# regsimple2addfp.net
KiCad netlist of a schematic drawn in EAGLE
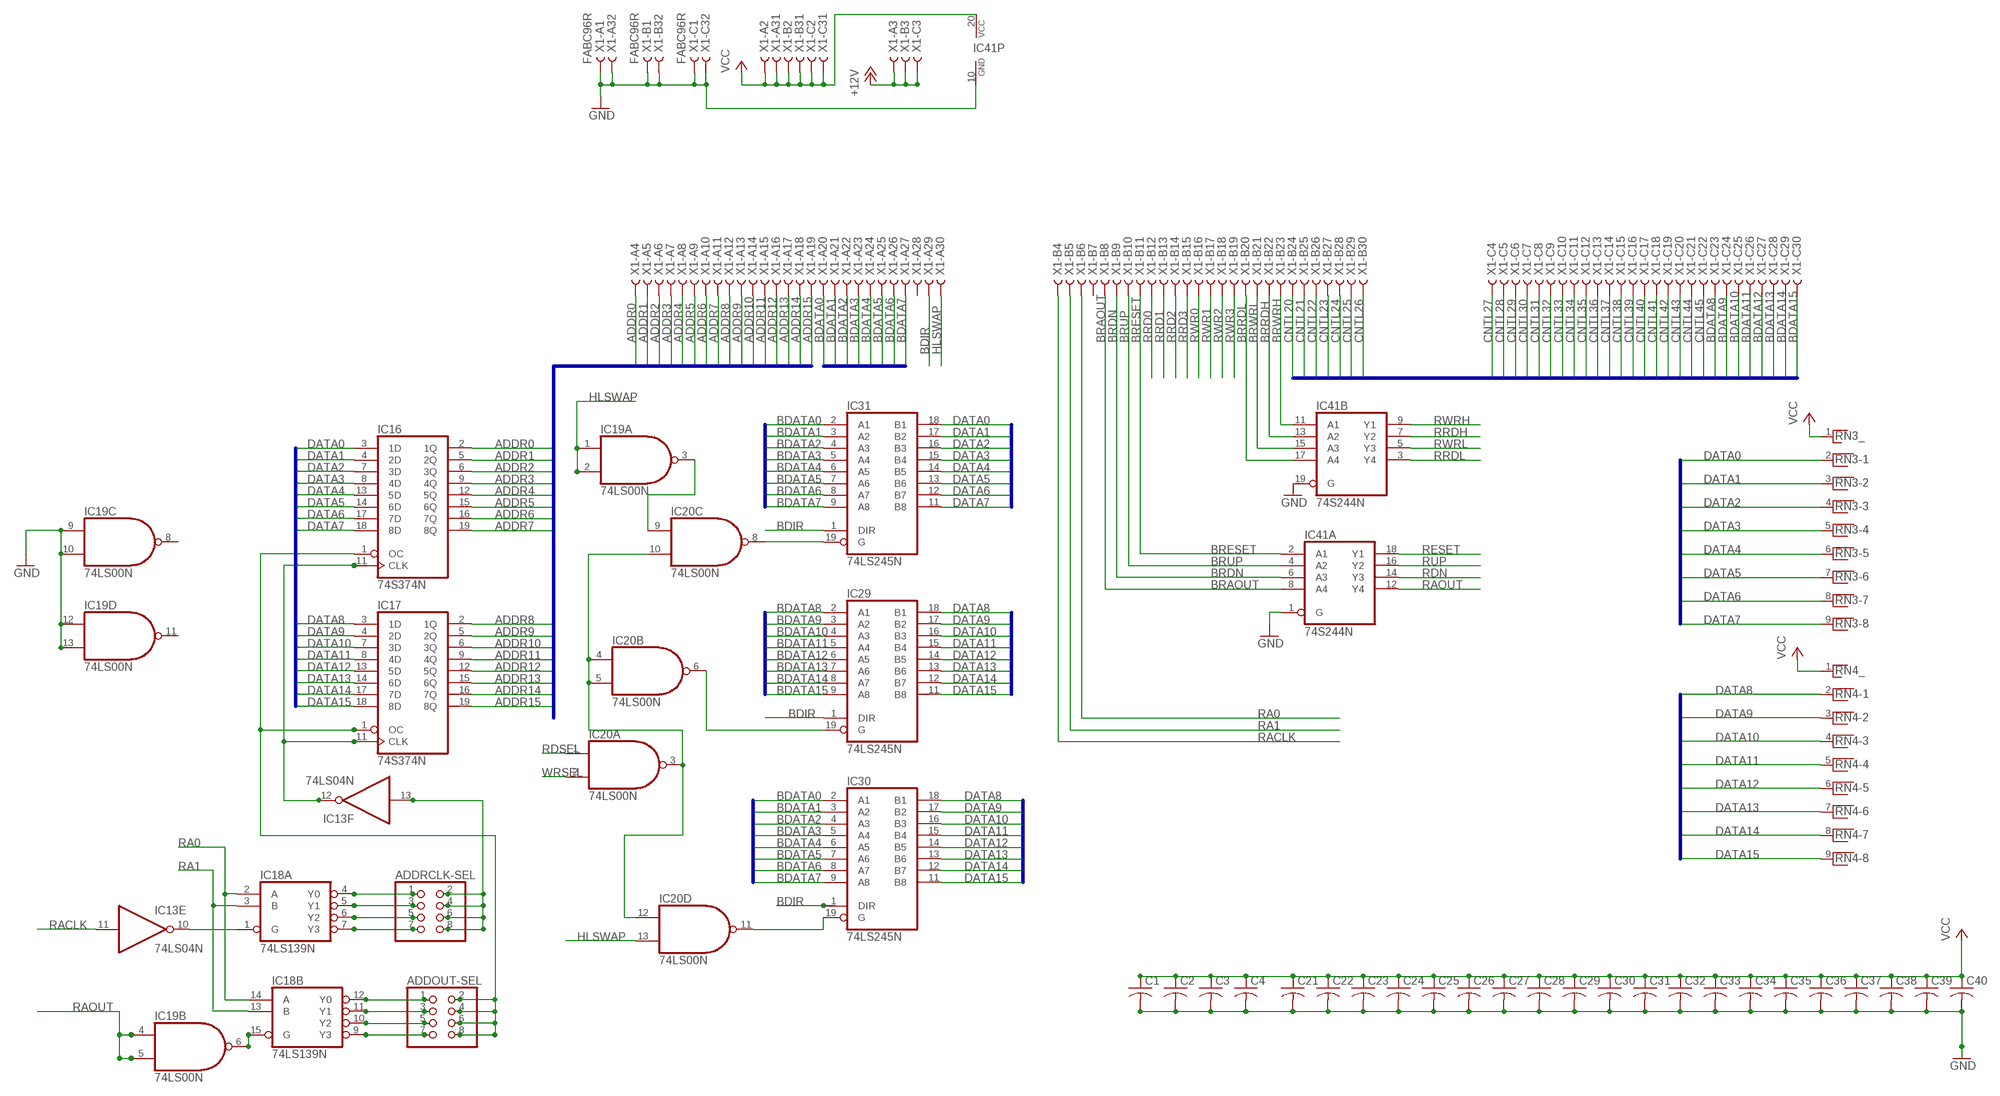
[diagram p0: schematic, sheet 1]
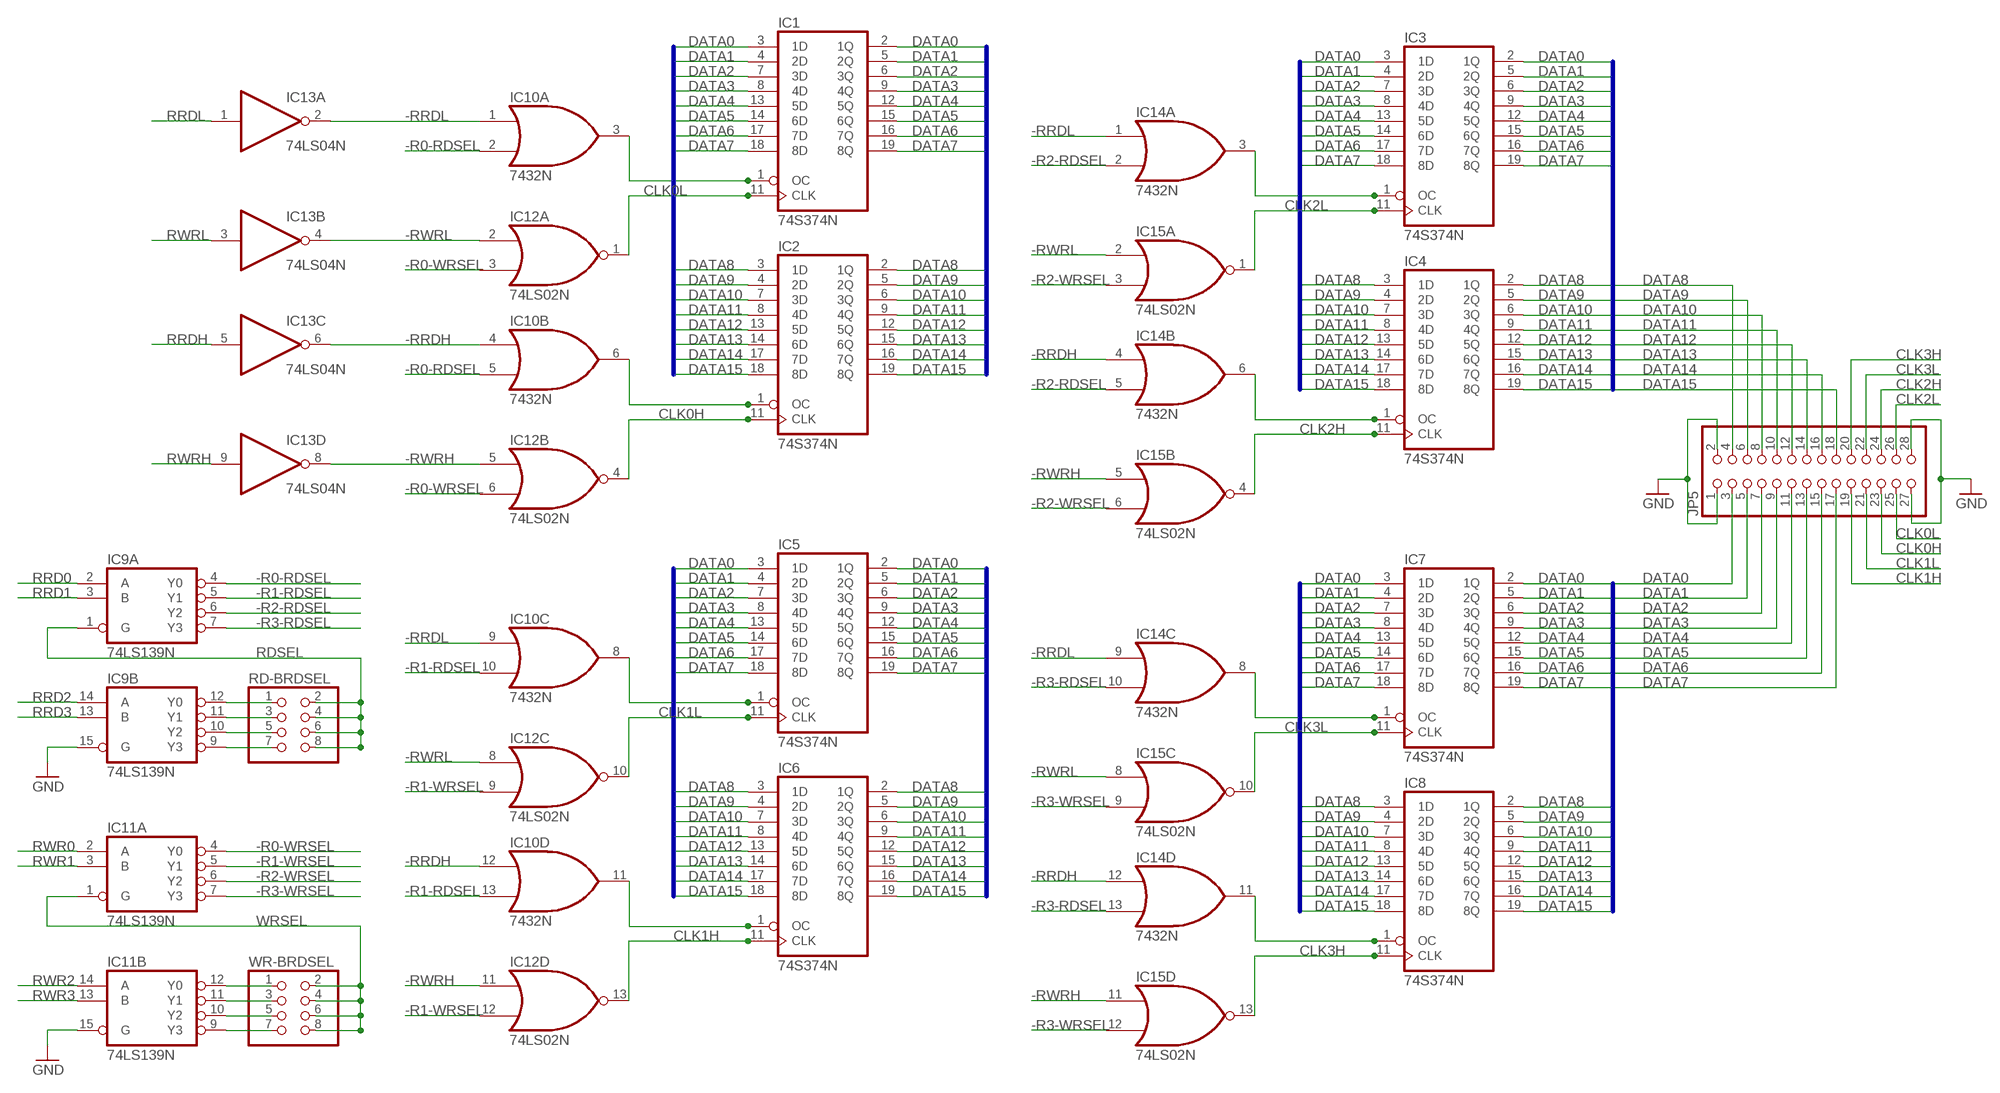
[diagram p1: schematic, sheet 2]

(export (version "E")
  (design (tool "Eeschema 10.0.6"))
  (components
    (comp (ref "ADDOUT-SEL")
      (value "PINHD-2X4")
      (footprint "eagle-import:2X04")
      (libsource (lib "eagle-import") (part "PINHD-2X4"))
    )
    (comp (ref "ADDRCLK-SEL")
      (value "PINHD-2X4")
      (footprint "eagle-import:2X04")
      (libsource (lib "eagle-import") (part "PINHD-2X4"))
    )
    (comp (ref "C1")
      (value "C-US025-040X050")
      (footprint "eagle-import:C025-040X050")
      (libsource (lib "eagle-import") (part "C-US025-040X050"))
    )
    (comp (ref "C2")
      (value "C-US025-040X050")
      (footprint "eagle-import:C025-040X050")
      (libsource (lib "eagle-import") (part "C-US025-040X050"))
    )
    (comp (ref "C3")
      (value "C-US025-040X050")
      (footprint "eagle-import:C025-040X050")
      (libsource (lib "eagle-import") (part "C-US025-040X050"))
    )
    (comp (ref "C4")
      (value "C-US025-040X050")
      (footprint "eagle-import:C025-040X050")
      (libsource (lib "eagle-import") (part "C-US025-040X050"))
    )
    (comp (ref "C21")
      (value "C-US025-040X050")
      (footprint "eagle-import:C025-040X050")
      (libsource (lib "eagle-import") (part "C-US025-040X050"))
    )
    (comp (ref "C22")
      (value "C-US025-040X050")
      (footprint "eagle-import:C025-040X050")
      (libsource (lib "eagle-import") (part "C-US025-040X050"))
    )
    (comp (ref "C23")
      (value "C-US025-040X050")
      (footprint "eagle-import:C025-040X050")
      (libsource (lib "eagle-import") (part "C-US025-040X050"))
    )
    (comp (ref "C24")
      (value "C-US025-040X050")
      (footprint "eagle-import:C025-040X050")
      (libsource (lib "eagle-import") (part "C-US025-040X050"))
    )
    (comp (ref "C25")
      (value "C-US025-040X050")
      (footprint "eagle-import:C025-040X050")
      (libsource (lib "eagle-import") (part "C-US025-040X050"))
    )
    (comp (ref "C26")
      (value "C-US025-040X050")
      (footprint "eagle-import:C025-040X050")
      (libsource (lib "eagle-import") (part "C-US025-040X050"))
    )
    (comp (ref "C27")
      (value "C-US025-040X050")
      (footprint "eagle-import:C025-040X050")
      (libsource (lib "eagle-import") (part "C-US025-040X050"))
    )
    (comp (ref "C28")
      (value "C-US025-040X050")
      (footprint "eagle-import:C025-040X050")
      (libsource (lib "eagle-import") (part "C-US025-040X050"))
    )
    (comp (ref "C29")
      (value "C-US025-040X050")
      (footprint "eagle-import:C025-040X050")
      (libsource (lib "eagle-import") (part "C-US025-040X050"))
    )
    (comp (ref "C30")
      (value "C-US025-040X050")
      (footprint "eagle-import:C025-040X050")
      (libsource (lib "eagle-import") (part "C-US025-040X050"))
    )
    (comp (ref "C31")
      (value "C-US025-040X050")
      (footprint "eagle-import:C025-040X050")
      (libsource (lib "eagle-import") (part "C-US025-040X050"))
    )
    (comp (ref "C32")
      (value "C-US025-040X050")
      (footprint "eagle-import:C025-040X050")
      (libsource (lib "eagle-import") (part "C-US025-040X050"))
    )
    (comp (ref "C33")
      (value "C-US025-040X050")
      (footprint "eagle-import:C025-040X050")
      (libsource (lib "eagle-import") (part "C-US025-040X050"))
    )
    (comp (ref "C34")
      (value "C-US025-040X050")
      (footprint "eagle-import:C025-040X050")
      (libsource (lib "eagle-import") (part "C-US025-040X050"))
    )
    (comp (ref "C35")
      (value "C-US025-040X050")
      (footprint "eagle-import:C025-040X050")
      (libsource (lib "eagle-import") (part "C-US025-040X050"))
    )
    (comp (ref "C36")
      (value "C-US025-040X050")
      (footprint "eagle-import:C025-040X050")
      (libsource (lib "eagle-import") (part "C-US025-040X050"))
    )
    (comp (ref "C37")
      (value "C-US025-040X050")
      (footprint "eagle-import:C025-040X050")
      (libsource (lib "eagle-import") (part "C-US025-040X050"))
    )
    (comp (ref "C38")
      (value "C-US025-040X050")
      (footprint "eagle-import:C025-040X050")
      (libsource (lib "eagle-import") (part "C-US025-040X050"))
    )
    (comp (ref "C39")
      (value "C-US025-040X050")
      (footprint "eagle-import:C025-040X050")
      (libsource (lib "eagle-import") (part "C-US025-040X050"))
    )
    (comp (ref "C40")
      (value "C-US025-040X050")
      (footprint "eagle-import:C025-040X050")
      (libsource (lib "eagle-import") (part "C-US025-040X050"))
    )
    (comp (ref "IC13")
      (value "74LS04N")
      (footprint "eagle-import:DIL14")
      (libsource (lib "eagle-import") (part "7404NLS"))
    )
    (comp (ref "IC16")
      (value "74S374N")
      (footprint "eagle-import:DIL20")
      (libsource (lib "eagle-import") (part "74374NS"))
    )
    (comp (ref "IC17")
      (value "74S374N")
      (footprint "eagle-import:DIL20")
      (libsource (lib "eagle-import") (part "74374NS"))
    )
    (comp (ref "IC18")
      (value "74LS139N")
      (footprint "eagle-import:DIL16")
      (libsource (lib "eagle-import") (part "74139NLS"))
    )
    (comp (ref "IC19")
      (value "74LS00N")
      (footprint "eagle-import:DIL14")
      (libsource (lib "eagle-import") (part "7400NLS"))
    )
    (comp (ref "IC20")
      (value "74LS00N")
      (footprint "eagle-import:DIL14")
      (libsource (lib "eagle-import") (part "7400NLS"))
    )
    (comp (ref "IC29")
      (value "74LS245N")
      (footprint "eagle-import:DIL20")
      (libsource (lib "eagle-import") (part "74245NLS"))
    )
    (comp (ref "IC30")
      (value "74LS245N")
      (footprint "eagle-import:DIL20")
      (libsource (lib "eagle-import") (part "74245NLS"))
    )
    (comp (ref "IC31")
      (value "74LS245N")
      (footprint "eagle-import:DIL20")
      (libsource (lib "eagle-import") (part "74245NLS"))
    )
    (comp (ref "IC41")
      (value "74S244N")
      (footprint "eagle-import:DIL20")
      (libsource (lib "eagle-import") (part "74244NS"))
    )
    (comp (ref "RN3")
      (value "RNX8")
      (footprint "eagle-import:RN-9")
      (libsource (lib "eagle-import") (part "RNX8"))
    )
    (comp (ref "RN4")
      (value "RNX8")
      (footprint "eagle-import:RN-9")
      (libsource (lib "eagle-import") (part "RNX8"))
    )
    (comp (ref "X1")
      (value "FABC96R")
      (footprint "eagle-import:FABC96R")
      (libsource (lib "eagle-import") (part "FABC96R"))
    )
    (comp (ref "IC1")
      (value "74S374N")
      (footprint "eagle-import:DIL20")
      (libsource (lib "eagle-import") (part "74374NS"))
    )
    (comp (ref "IC2")
      (value "74S374N")
      (footprint "eagle-import:DIL20")
      (libsource (lib "eagle-import") (part "74374NS"))
    )
    (comp (ref "IC3")
      (value "74S374N")
      (footprint "eagle-import:DIL20")
      (libsource (lib "eagle-import") (part "74374NS"))
    )
    (comp (ref "IC4")
      (value "74S374N")
      (footprint "eagle-import:DIL20")
      (libsource (lib "eagle-import") (part "74374NS"))
    )
    (comp (ref "IC5")
      (value "74S374N")
      (footprint "eagle-import:DIL20")
      (libsource (lib "eagle-import") (part "74374NS"))
    )
    (comp (ref "IC6")
      (value "74S374N")
      (footprint "eagle-import:DIL20")
      (libsource (lib "eagle-import") (part "74374NS"))
    )
    (comp (ref "IC7")
      (value "74S374N")
      (footprint "eagle-import:DIL20")
      (libsource (lib "eagle-import") (part "74374NS"))
    )
    (comp (ref "IC8")
      (value "74S374N")
      (footprint "eagle-import:DIL20")
      (libsource (lib "eagle-import") (part "74374NS"))
    )
    (comp (ref "IC9")
      (value "74LS139N")
      (footprint "eagle-import:DIL16")
      (libsource (lib "eagle-import") (part "74139NLS"))
    )
    (comp (ref "IC10")
      (value "7432N")
      (footprint "eagle-import:DIL14")
      (libsource (lib "eagle-import") (part "7432N"))
    )
    (comp (ref "IC11")
      (value "74LS139N")
      (footprint "eagle-import:DIL16")
      (libsource (lib "eagle-import") (part "74139NLS"))
    )
    (comp (ref "IC12")
      (value "74LS02N")
      (footprint "eagle-import:DIL14")
      (libsource (lib "eagle-import") (part "7402NLS"))
    )
    (comp (ref "IC14")
      (value "7432N")
      (footprint "eagle-import:DIL14")
      (libsource (lib "eagle-import") (part "7432N"))
    )
    (comp (ref "IC15")
      (value "74LS02N")
      (footprint "eagle-import:DIL14")
      (libsource (lib "eagle-import") (part "7402NLS"))
    )
    (comp (ref "JP5")
      (value "PINHD-2X14")
      (footprint "eagle-import:2X14")
      (libsource (lib "eagle-import") (part "PINHD-2X14"))
    )
    (comp (ref "RD-BRDSEL")
      (value "PINHD-2X4")
      (footprint "eagle-import:2X04")
      (libsource (lib "eagle-import") (part "PINHD-2X4"))
    )
    (comp (ref "WR-BRDSEL")
      (value "PINHD-2X4")
      (footprint "eagle-import:2X04")
      (libsource (lib "eagle-import") (part "PINHD-2X4"))
    )
  )
  (nets
    (net (code "1") (name "+12V") (class "Default")
      (node (ref "X1") (pin "A3") (pinfunction "B_A3") (pintype "passive"))
      (node (ref "X1") (pin "B3") (pinfunction "B_B3") (pintype "passive"))
      (node (ref "X1") (pin "C3") (pinfunction "B_C3") (pintype "passive"))
    )
    (net (code "2") (name "-R0-RDSEL") (class "Default")
      (node (ref "IC10") (pin "2") (pinfunction "I1_2") (pintype "input"))
      (node (ref "IC10") (pin "5") (pinfunction "I1_5") (pintype "input"))
      (node (ref "IC9") (pin "4") (pinfunction "Y0_4") (pintype "output"))
    )
    (net (code "3") (name "-R0-WRSEL") (class "Default")
      (node (ref "IC11") (pin "4") (pinfunction "Y0_4") (pintype "output"))
      (node (ref "IC12") (pin "3") (pinfunction "I1_3") (pintype "input"))
      (node (ref "IC12") (pin "6") (pinfunction "I1_6") (pintype "input"))
    )
    (net (code "4") (name "-R1-RDSEL") (class "Default")
      (node (ref "IC10") (pin "10") (pinfunction "I1_10") (pintype "input"))
      (node (ref "IC10") (pin "13") (pinfunction "I1_13") (pintype "input"))
      (node (ref "IC9") (pin "5") (pinfunction "Y1_5") (pintype "output"))
    )
    (net (code "5") (name "-R1-WRSEL") (class "Default")
      (node (ref "IC11") (pin "5") (pinfunction "Y1_5") (pintype "output"))
      (node (ref "IC12") (pin "12") (pinfunction "I1_12") (pintype "input"))
      (node (ref "IC12") (pin "9") (pinfunction "I1_9") (pintype "input"))
    )
    (net (code "6") (name "-R2-RDSEL") (class "Default")
      (node (ref "IC14") (pin "2") (pinfunction "I1_2") (pintype "input"))
      (node (ref "IC14") (pin "5") (pinfunction "I1_5") (pintype "input"))
      (node (ref "IC9") (pin "6") (pinfunction "Y2_6") (pintype "output"))
    )
    (net (code "7") (name "-R2-WRSEL") (class "Default")
      (node (ref "IC11") (pin "6") (pinfunction "Y2_6") (pintype "output"))
      (node (ref "IC15") (pin "3") (pinfunction "I1_3") (pintype "input"))
      (node (ref "IC15") (pin "6") (pinfunction "I1_6") (pintype "input"))
    )
    (net (code "8") (name "-R3-RDSEL") (class "Default")
      (node (ref "IC14") (pin "10") (pinfunction "I1_10") (pintype "input"))
      (node (ref "IC14") (pin "13") (pinfunction "I1_13") (pintype "input"))
      (node (ref "IC9") (pin "7") (pinfunction "Y3_7") (pintype "output"))
    )
    (net (code "9") (name "-R3-WRSEL") (class "Default")
      (node (ref "IC11") (pin "7") (pinfunction "Y3_7") (pintype "output"))
      (node (ref "IC15") (pin "12") (pinfunction "I1_12") (pintype "input"))
      (node (ref "IC15") (pin "9") (pinfunction "I1_9") (pintype "input"))
    )
    (net (code "10") (name "-RRDH") (class "Default")
      (node (ref "IC10") (pin "12") (pinfunction "I0_12") (pintype "input"))
      (node (ref "IC10") (pin "4") (pinfunction "I0_4") (pintype "input"))
      (node (ref "IC13") (pin "6") (pinfunction "O_6") (pintype "output"))
      (node (ref "IC14") (pin "12") (pinfunction "I0_12") (pintype "input"))
      (node (ref "IC14") (pin "4") (pinfunction "I0_4") (pintype "input"))
    )
    (net (code "11") (name "-RRDL") (class "Default")
      (node (ref "IC10") (pin "1") (pinfunction "I0_1") (pintype "input"))
      (node (ref "IC10") (pin "9") (pinfunction "I0_9") (pintype "input"))
      (node (ref "IC13") (pin "2") (pinfunction "O_2") (pintype "output"))
      (node (ref "IC14") (pin "1") (pinfunction "I0_1") (pintype "input"))
      (node (ref "IC14") (pin "9") (pinfunction "I0_9") (pintype "input"))
    )
    (net (code "12") (name "-RWRH") (class "Default")
      (node (ref "IC12") (pin "11") (pinfunction "I0_11") (pintype "input"))
      (node (ref "IC12") (pin "5") (pinfunction "I0_5") (pintype "input"))
      (node (ref "IC13") (pin "8") (pinfunction "O_8") (pintype "output"))
      (node (ref "IC15") (pin "11") (pinfunction "I0_11") (pintype "input"))
      (node (ref "IC15") (pin "5") (pinfunction "I0_5") (pintype "input"))
    )
    (net (code "13") (name "-RWRL") (class "Default")
      (node (ref "IC12") (pin "2") (pinfunction "I0_2") (pintype "input"))
      (node (ref "IC12") (pin "8") (pinfunction "I0_8") (pintype "input"))
      (node (ref "IC13") (pin "4") (pinfunction "O_4") (pintype "output"))
      (node (ref "IC15") (pin "2") (pinfunction "I0_2") (pintype "input"))
      (node (ref "IC15") (pin "8") (pinfunction "I0_8") (pintype "input"))
    )
    (net (code "14") (name "ADDR0") (class "Default")
      (node (ref "IC16") (pin "2") (pinfunction "1Q_2") (pintype "tri_state"))
      (node (ref "X1") (pin "A4") (pinfunction "B_A4") (pintype "passive"))
    )
    (net (code "15") (name "ADDR1") (class "Default")
      (node (ref "IC16") (pin "5") (pinfunction "2Q_5") (pintype "tri_state"))
      (node (ref "X1") (pin "A5") (pinfunction "B_A5") (pintype "passive"))
    )
    (net (code "16") (name "ADDR2") (class "Default")
      (node (ref "IC16") (pin "6") (pinfunction "3Q_6") (pintype "tri_state"))
      (node (ref "X1") (pin "A6") (pinfunction "B_A6") (pintype "passive"))
    )
    (net (code "17") (name "ADDR3") (class "Default")
      (node (ref "IC16") (pin "9") (pinfunction "4Q_9") (pintype "tri_state"))
      (node (ref "X1") (pin "A7") (pinfunction "B_A7") (pintype "passive"))
    )
    (net (code "18") (name "ADDR4") (class "Default")
      (node (ref "IC16") (pin "12") (pinfunction "5Q_12") (pintype "tri_state"))
      (node (ref "X1") (pin "A8") (pinfunction "B_A8") (pintype "passive"))
    )
    (net (code "19") (name "ADDR5") (class "Default")
      (node (ref "IC16") (pin "15") (pinfunction "6Q_15") (pintype "tri_state"))
      (node (ref "X1") (pin "A9") (pinfunction "B_A9") (pintype "passive"))
    )
    (net (code "20") (name "ADDR6") (class "Default")
      (node (ref "IC16") (pin "16") (pinfunction "7Q_16") (pintype "tri_state"))
      (node (ref "X1") (pin "A10") (pinfunction "B_A10") (pintype "passive"))
    )
    (net (code "21") (name "ADDR7") (class "Default")
      (node (ref "IC16") (pin "19") (pinfunction "8Q_19") (pintype "tri_state"))
      (node (ref "X1") (pin "A11") (pinfunction "B_A11") (pintype "passive"))
    )
    (net (code "22") (name "ADDR8") (class "Default")
      (node (ref "IC17") (pin "2") (pinfunction "1Q_2") (pintype "tri_state"))
      (node (ref "X1") (pin "A12") (pinfunction "B_A12") (pintype "passive"))
    )
    (net (code "23") (name "ADDR9") (class "Default")
      (node (ref "IC17") (pin "5") (pinfunction "2Q_5") (pintype "tri_state"))
      (node (ref "X1") (pin "A13") (pinfunction "B_A13") (pintype "passive"))
    )
    (net (code "24") (name "ADDR10") (class "Default")
      (node (ref "IC17") (pin "6") (pinfunction "3Q_6") (pintype "tri_state"))
      (node (ref "X1") (pin "A14") (pinfunction "B_A14") (pintype "passive"))
    )
    (net (code "25") (name "ADDR11") (class "Default")
      (node (ref "IC17") (pin "9") (pinfunction "4Q_9") (pintype "tri_state"))
      (node (ref "X1") (pin "A15") (pinfunction "B_A15") (pintype "passive"))
    )
    (net (code "26") (name "ADDR12") (class "Default")
      (node (ref "IC17") (pin "12") (pinfunction "5Q_12") (pintype "tri_state"))
      (node (ref "X1") (pin "A16") (pinfunction "B_A16") (pintype "passive"))
    )
    (net (code "27") (name "ADDR13") (class "Default")
      (node (ref "IC17") (pin "15") (pinfunction "6Q_15") (pintype "tri_state"))
      (node (ref "X1") (pin "A17") (pinfunction "B_A17") (pintype "passive"))
    )
    (net (code "28") (name "ADDR14") (class "Default")
      (node (ref "IC17") (pin "16") (pinfunction "7Q_16") (pintype "tri_state"))
      (node (ref "X1") (pin "A18") (pinfunction "B_A18") (pintype "passive"))
    )
    (net (code "29") (name "ADDR15") (class "Default")
      (node (ref "IC17") (pin "19") (pinfunction "8Q_19") (pintype "tri_state"))
      (node (ref "X1") (pin "A19") (pinfunction "B_A19") (pintype "passive"))
    )
    (net (code "30") (name "BDATA0") (class "Default")
      (node (ref "IC30") (pin "2") (pinfunction "A1_2") (pintype "bidirectional"))
      (node (ref "IC31") (pin "2") (pinfunction "A1_2") (pintype "bidirectional"))
      (node (ref "X1") (pin "A20") (pinfunction "B_A20") (pintype "passive"))
    )
    (net (code "31") (name "BDATA1") (class "Default")
      (node (ref "IC30") (pin "3") (pinfunction "A2_3") (pintype "bidirectional"))
      (node (ref "IC31") (pin "3") (pinfunction "A2_3") (pintype "bidirectional"))
      (node (ref "X1") (pin "A21") (pinfunction "B_A21") (pintype "passive"))
    )
    (net (code "32") (name "BDATA2") (class "Default")
      (node (ref "IC30") (pin "4") (pinfunction "A3_4") (pintype "bidirectional"))
      (node (ref "IC31") (pin "4") (pinfunction "A3_4") (pintype "bidirectional"))
      (node (ref "X1") (pin "A22") (pinfunction "B_A22") (pintype "passive"))
    )
    (net (code "33") (name "BDATA3") (class "Default")
      (node (ref "IC30") (pin "5") (pinfunction "A4_5") (pintype "bidirectional"))
      (node (ref "IC31") (pin "5") (pinfunction "A4_5") (pintype "bidirectional"))
      (node (ref "X1") (pin "A23") (pinfunction "B_A23") (pintype "passive"))
    )
    (net (code "34") (name "BDATA4") (class "Default")
      (node (ref "IC30") (pin "6") (pinfunction "A5_6") (pintype "bidirectional"))
      (node (ref "IC31") (pin "6") (pinfunction "A5_6") (pintype "bidirectional"))
      (node (ref "X1") (pin "A24") (pinfunction "B_A24") (pintype "passive"))
    )
    (net (code "35") (name "BDATA5") (class "Default")
      (node (ref "IC30") (pin "7") (pinfunction "A6_7") (pintype "bidirectional"))
      (node (ref "IC31") (pin "7") (pinfunction "A6_7") (pintype "bidirectional"))
      (node (ref "X1") (pin "A25") (pinfunction "B_A25") (pintype "passive"))
    )
    (net (code "36") (name "BDATA6") (class "Default")
      (node (ref "IC30") (pin "8") (pinfunction "A7_8") (pintype "bidirectional"))
      (node (ref "IC31") (pin "8") (pinfunction "A7_8") (pintype "bidirectional"))
      (node (ref "X1") (pin "A26") (pinfunction "B_A26") (pintype "passive"))
    )
    (net (code "37") (name "BDATA7") (class "Default")
      (node (ref "IC30") (pin "9") (pinfunction "A8_9") (pintype "bidirectional"))
      (node (ref "IC31") (pin "9") (pinfunction "A8_9") (pintype "bidirectional"))
      (node (ref "X1") (pin "A27") (pinfunction "B_A27") (pintype "passive"))
    )
    (net (code "38") (name "BDATA8") (class "Default")
      (node (ref "IC29") (pin "2") (pinfunction "A1_2") (pintype "bidirectional"))
      (node (ref "X1") (pin "C23") (pinfunction "B_C23") (pintype "passive"))
    )
    (net (code "39") (name "BDATA9") (class "Default")
      (node (ref "IC29") (pin "3") (pinfunction "A2_3") (pintype "bidirectional"))
      (node (ref "X1") (pin "C24") (pinfunction "B_C24") (pintype "passive"))
    )
    (net (code "40") (name "BDATA10") (class "Default")
      (node (ref "IC29") (pin "4") (pinfunction "A3_4") (pintype "bidirectional"))
      (node (ref "X1") (pin "C25") (pinfunction "B_C25") (pintype "passive"))
    )
    (net (code "41") (name "BDATA11") (class "Default")
      (node (ref "IC29") (pin "5") (pinfunction "A4_5") (pintype "bidirectional"))
      (node (ref "X1") (pin "C26") (pinfunction "B_C26") (pintype "passive"))
    )
    (net (code "42") (name "BDATA12") (class "Default")
      (node (ref "IC29") (pin "6") (pinfunction "A5_6") (pintype "bidirectional"))
      (node (ref "X1") (pin "C27") (pinfunction "B_C27") (pintype "passive"))
    )
    (net (code "43") (name "BDATA13") (class "Default")
      (node (ref "IC29") (pin "7") (pinfunction "A6_7") (pintype "bidirectional"))
      (node (ref "X1") (pin "C28") (pinfunction "B_C28") (pintype "passive"))
    )
    (net (code "44") (name "BDATA14") (class "Default")
      (node (ref "IC29") (pin "8") (pinfunction "A7_8") (pintype "bidirectional"))
      (node (ref "X1") (pin "C29") (pinfunction "B_C29") (pintype "passive"))
    )
    (net (code "45") (name "BDATA15") (class "Default")
      (node (ref "IC29") (pin "9") (pinfunction "A8_9") (pintype "bidirectional"))
      (node (ref "X1") (pin "C30") (pinfunction "B_C30") (pintype "passive"))
    )
    (net (code "46") (name "BDIR") (class "Default")
      (node (ref "IC29") (pin "1") (pinfunction "DIR_1") (pintype "input"))
      (node (ref "IC30") (pin "1") (pinfunction "DIR_1") (pintype "input"))
      (node (ref "IC31") (pin "1") (pinfunction "DIR_1") (pintype "input"))
      (node (ref "X1") (pin "A29") (pinfunction "B_A29") (pintype "passive"))
    )
    (net (code "47") (name "BRAOUT") (class "Default")
      (node (ref "IC41") (pin "8") (pinfunction "A4_8") (pintype "input"))
      (node (ref "X1") (pin "B8") (pinfunction "B_B8") (pintype "passive"))
    )
    (net (code "48") (name "BRDN") (class "Default")
      (node (ref "IC41") (pin "6") (pinfunction "A3_6") (pintype "input"))
      (node (ref "X1") (pin "B9") (pinfunction "B_B9") (pintype "passive"))
    )
    (net (code "49") (name "BRESET") (class "Default")
      (node (ref "IC41") (pin "2") (pinfunction "A1_2") (pintype "input"))
      (node (ref "X1") (pin "B11") (pinfunction "B_B11") (pintype "passive"))
    )
    (net (code "50") (name "BRRDH") (class "Default")
      (node (ref "IC41") (pin "13") (pinfunction "A2_13") (pintype "input"))
      (node (ref "X1") (pin "B22") (pinfunction "B_B22") (pintype "passive"))
    )
    (net (code "51") (name "BRRDL") (class "Default")
      (node (ref "IC41") (pin "17") (pinfunction "A4_17") (pintype "input"))
      (node (ref "X1") (pin "B20") (pinfunction "B_B20") (pintype "passive"))
    )
    (net (code "52") (name "BRUP") (class "Default")
      (node (ref "IC41") (pin "4") (pinfunction "A2_4") (pintype "input"))
      (node (ref "X1") (pin "B10") (pinfunction "B_B10") (pintype "passive"))
    )
    (net (code "53") (name "BRWRH") (class "Default")
      (node (ref "IC41") (pin "11") (pinfunction "A1_11") (pintype "input"))
      (node (ref "X1") (pin "B23") (pinfunction "B_B23") (pintype "passive"))
    )
    (net (code "54") (name "BRWRL") (class "Default")
      (node (ref "IC41") (pin "15") (pinfunction "A3_15") (pintype "input"))
      (node (ref "X1") (pin "B21") (pinfunction "B_B21") (pintype "passive"))
    )
    (net (code "55") (name "CLK0H") (class "Default")
      (node (ref "IC12") (pin "4") (pinfunction "O_4") (pintype "output"))
      (node (ref "IC2") (pin "11") (pinfunction "CLK_11") (pintype "input"))
      (node (ref "JP5") (pin "23") (pinfunction "23_23") (pintype "passive"))
    )
    (net (code "56") (name "CLK0L") (class "Default")
      (node (ref "IC1") (pin "11") (pinfunction "CLK_11") (pintype "input"))
      (node (ref "IC12") (pin "1") (pinfunction "O_1") (pintype "output"))
      (node (ref "JP5") (pin "25") (pinfunction "25_25") (pintype "passive"))
    )
    (net (code "57") (name "CLK1H") (class "Default")
      (node (ref "IC12") (pin "13") (pinfunction "O_13") (pintype "output"))
      (node (ref "IC6") (pin "11") (pinfunction "CLK_11") (pintype "input"))
      (node (ref "JP5") (pin "19") (pinfunction "19_19") (pintype "passive"))
    )
    (net (code "58") (name "CLK1L") (class "Default")
      (node (ref "IC12") (pin "10") (pinfunction "O_10") (pintype "output"))
      (node (ref "IC5") (pin "11") (pinfunction "CLK_11") (pintype "input"))
      (node (ref "JP5") (pin "21") (pinfunction "21_21") (pintype "passive"))
    )
    (net (code "59") (name "CLK2H") (class "Default")
      (node (ref "IC15") (pin "4") (pinfunction "O_4") (pintype "output"))
      (node (ref "IC4") (pin "11") (pinfunction "CLK_11") (pintype "input"))
      (node (ref "JP5") (pin "24") (pinfunction "24_24") (pintype "passive"))
    )
    (net (code "60") (name "CLK2L") (class "Default")
      (node (ref "IC15") (pin "1") (pinfunction "O_1") (pintype "output"))
      (node (ref "IC3") (pin "11") (pinfunction "CLK_11") (pintype "input"))
      (node (ref "JP5") (pin "26") (pinfunction "26_26") (pintype "passive"))
    )
    (net (code "61") (name "CLK3H") (class "Default")
      (node (ref "IC15") (pin "13") (pinfunction "O_13") (pintype "output"))
      (node (ref "IC8") (pin "11") (pinfunction "CLK_11") (pintype "input"))
      (node (ref "JP5") (pin "20") (pinfunction "20_20") (pintype "passive"))
    )
    (net (code "62") (name "CLK3L") (class "Default")
      (node (ref "IC15") (pin "10") (pinfunction "O_10") (pintype "output"))
      (node (ref "IC7") (pin "11") (pinfunction "CLK_11") (pintype "input"))
      (node (ref "JP5") (pin "22") (pinfunction "22_22") (pintype "passive"))
    )
    (net (code "63") (name "CNTL20") (class "Default")
      (node (ref "X1") (pin "B24") (pinfunction "B_B24") (pintype "passive"))
    )
    (net (code "64") (name "CNTL21") (class "Default")
      (node (ref "X1") (pin "B25") (pinfunction "B_B25") (pintype "passive"))
    )
    (net (code "65") (name "CNTL22") (class "Default")
      (node (ref "X1") (pin "B26") (pinfunction "B_B26") (pintype "passive"))
    )
    (net (code "66") (name "CNTL23") (class "Default")
      (node (ref "X1") (pin "B27") (pinfunction "B_B27") (pintype "passive"))
    )
    (net (code "67") (name "CNTL24") (class "Default")
      (node (ref "X1") (pin "B28") (pinfunction "B_B28") (pintype "passive"))
    )
    (net (code "68") (name "CNTL25") (class "Default")
      (node (ref "X1") (pin "B29") (pinfunction "B_B29") (pintype "passive"))
    )
    (net (code "69") (name "CNTL26") (class "Default")
      (node (ref "X1") (pin "B30") (pinfunction "B_B30") (pintype "passive"))
    )
    (net (code "70") (name "CNTL27") (class "Default")
      (node (ref "X1") (pin "C4") (pinfunction "B_C4") (pintype "passive"))
    )
    (net (code "71") (name "CNTL28") (class "Default")
      (node (ref "X1") (pin "C5") (pinfunction "B_C5") (pintype "passive"))
    )
    (net (code "72") (name "CNTL29") (class "Default")
      (node (ref "X1") (pin "C6") (pinfunction "B_C6") (pintype "passive"))
    )
    (net (code "73") (name "CNTL30") (class "Default")
      (node (ref "X1") (pin "C7") (pinfunction "B_C7") (pintype "passive"))
    )
    (net (code "74") (name "CNTL31") (class "Default")
      (node (ref "X1") (pin "C8") (pinfunction "B_C8") (pintype "passive"))
    )
    (net (code "75") (name "CNTL32") (class "Default")
      (node (ref "X1") (pin "C9") (pinfunction "B_C9") (pintype "passive"))
    )
    (net (code "76") (name "CNTL33") (class "Default")
      (node (ref "X1") (pin "C10") (pinfunction "B_C10") (pintype "passive"))
    )
    (net (code "77") (name "CNTL34") (class "Default")
      (node (ref "X1") (pin "C11") (pinfunction "B_C11") (pintype "passive"))
    )
    (net (code "78") (name "CNTL35") (class "Default")
      (node (ref "X1") (pin "C12") (pinfunction "B_C12") (pintype "passive"))
    )
    (net (code "79") (name "CNTL36") (class "Default")
      (node (ref "X1") (pin "C13") (pinfunction "B_C13") (pintype "passive"))
    )
    (net (code "80") (name "CNTL37") (class "Default")
      (node (ref "X1") (pin "C14") (pinfunction "B_C14") (pintype "passive"))
    )
    (net (code "81") (name "CNTL38") (class "Default")
      (node (ref "X1") (pin "C15") (pinfunction "B_C15") (pintype "passive"))
    )
    (net (code "82") (name "CNTL39") (class "Default")
      (node (ref "X1") (pin "C16") (pinfunction "B_C16") (pintype "passive"))
    )
    (net (code "83") (name "CNTL40") (class "Default")
      (node (ref "X1") (pin "C17") (pinfunction "B_C17") (pintype "passive"))
    )
    (net (code "84") (name "CNTL41") (class "Default")
      (node (ref "X1") (pin "C18") (pinfunction "B_C18") (pintype "passive"))
    )
    (net (code "85") (name "CNTL42") (class "Default")
      (node (ref "X1") (pin "C19") (pinfunction "B_C19") (pintype "passive"))
    )
    (net (code "86") (name "CNTL43") (class "Default")
      (node (ref "X1") (pin "C20") (pinfunction "B_C20") (pintype "passive"))
    )
    (net (code "87") (name "CNTL44") (class "Default")
      (node (ref "X1") (pin "C21") (pinfunction "B_C21") (pintype "passive"))
    )
    (net (code "88") (name "CNTL45") (class "Default")
      (node (ref "X1") (pin "C22") (pinfunction "B_C22") (pintype "passive"))
    )
    (net (code "89") (name "DATA0") (class "Default")
      (node (ref "IC1") (pin "2") (pinfunction "1Q_2") (pintype "tri_state"))
      (node (ref "IC1") (pin "3") (pinfunction "1D_3") (pintype "input"))
      (node (ref "IC16") (pin "3") (pinfunction "1D_3") (pintype "input"))
      (node (ref "IC3") (pin "2") (pinfunction "1Q_2") (pintype "tri_state"))
      (node (ref "IC3") (pin "3") (pinfunction "1D_3") (pintype "input"))
      (node (ref "IC31") (pin "18") (pinfunction "B1_18") (pintype "bidirectional"))
      (node (ref "IC5") (pin "2") (pinfunction "1Q_2") (pintype "tri_state"))
      (node (ref "IC5") (pin "3") (pinfunction "1D_3") (pintype "input"))
      (node (ref "IC7") (pin "2") (pinfunction "1Q_2") (pintype "tri_state"))
      (node (ref "IC7") (pin "3") (pinfunction "1D_3") (pintype "input"))
      (node (ref "JP5") (pin "3") (pinfunction "3_3") (pintype "passive"))
      (node (ref "RN3") (pin "2") (pinfunction "1_2") (pintype "passive"))
    )
    (net (code "90") (name "DATA1") (class "Default")
      (node (ref "IC1") (pin "4") (pinfunction "2D_4") (pintype "input"))
      (node (ref "IC1") (pin "5") (pinfunction "2Q_5") (pintype "tri_state"))
      (node (ref "IC16") (pin "4") (pinfunction "2D_4") (pintype "input"))
      (node (ref "IC3") (pin "4") (pinfunction "2D_4") (pintype "input"))
      (node (ref "IC3") (pin "5") (pinfunction "2Q_5") (pintype "tri_state"))
      (node (ref "IC31") (pin "17") (pinfunction "B2_17") (pintype "bidirectional"))
      (node (ref "IC5") (pin "4") (pinfunction "2D_4") (pintype "input"))
      (node (ref "IC5") (pin "5") (pinfunction "2Q_5") (pintype "tri_state"))
      (node (ref "IC7") (pin "4") (pinfunction "2D_4") (pintype "input"))
      (node (ref "IC7") (pin "5") (pinfunction "2Q_5") (pintype "tri_state"))
      (node (ref "JP5") (pin "5") (pinfunction "5_5") (pintype "passive"))
      (node (ref "RN3") (pin "3") (pinfunction "1_3") (pintype "passive"))
    )
    (net (code "91") (name "DATA2") (class "Default")
      (node (ref "IC1") (pin "6") (pinfunction "3Q_6") (pintype "tri_state"))
      (node (ref "IC1") (pin "7") (pinfunction "3D_7") (pintype "input"))
      (node (ref "IC16") (pin "7") (pinfunction "3D_7") (pintype "input"))
      (node (ref "IC3") (pin "6") (pinfunction "3Q_6") (pintype "tri_state"))
      (node (ref "IC3") (pin "7") (pinfunction "3D_7") (pintype "input"))
      (node (ref "IC31") (pin "16") (pinfunction "B3_16") (pintype "bidirectional"))
      (node (ref "IC5") (pin "6") (pinfunction "3Q_6") (pintype "tri_state"))
      (node (ref "IC5") (pin "7") (pinfunction "3D_7") (pintype "input"))
      (node (ref "IC7") (pin "6") (pinfunction "3Q_6") (pintype "tri_state"))
      (node (ref "IC7") (pin "7") (pinfunction "3D_7") (pintype "input"))
      (node (ref "JP5") (pin "7") (pinfunction "7_7") (pintype "passive"))
      (node (ref "RN3") (pin "4") (pinfunction "1_4") (pintype "passive"))
    )
    (net (code "92") (name "DATA3") (class "Default")
      (node (ref "IC1") (pin "8") (pinfunction "4D_8") (pintype "input"))
      (node (ref "IC1") (pin "9") (pinfunction "4Q_9") (pintype "tri_state"))
      (node (ref "IC16") (pin "8") (pinfunction "4D_8") (pintype "input"))
      (node (ref "IC3") (pin "8") (pinfunction "4D_8") (pintype "input"))
      (node (ref "IC3") (pin "9") (pinfunction "4Q_9") (pintype "tri_state"))
      (node (ref "IC31") (pin "15") (pinfunction "B4_15") (pintype "bidirectional"))
      (node (ref "IC5") (pin "8") (pinfunction "4D_8") (pintype "input"))
      (node (ref "IC5") (pin "9") (pinfunction "4Q_9") (pintype "tri_state"))
      (node (ref "IC7") (pin "8") (pinfunction "4D_8") (pintype "input"))
      (node (ref "IC7") (pin "9") (pinfunction "4Q_9") (pintype "tri_state"))
      (node (ref "JP5") (pin "9") (pinfunction "9_9") (pintype "passive"))
      (node (ref "RN3") (pin "5") (pinfunction "1_5") (pintype "passive"))
    )
    (net (code "93") (name "DATA4") (class "Default")
      (node (ref "IC1") (pin "12") (pinfunction "5Q_12") (pintype "tri_state"))
      (node (ref "IC1") (pin "13") (pinfunction "5D_13") (pintype "input"))
      (node (ref "IC16") (pin "13") (pinfunction "5D_13") (pintype "input"))
      (node (ref "IC3") (pin "12") (pinfunction "5Q_12") (pintype "tri_state"))
      (node (ref "IC3") (pin "13") (pinfunction "5D_13") (pintype "input"))
      (node (ref "IC31") (pin "14") (pinfunction "B5_14") (pintype "bidirectional"))
      (node (ref "IC5") (pin "12") (pinfunction "5Q_12") (pintype "tri_state"))
      (node (ref "IC5") (pin "13") (pinfunction "5D_13") (pintype "input"))
      (node (ref "IC7") (pin "12") (pinfunction "5Q_12") (pintype "tri_state"))
      (node (ref "IC7") (pin "13") (pinfunction "5D_13") (pintype "input"))
      (node (ref "JP5") (pin "11") (pinfunction "11_11") (pintype "passive"))
      (node (ref "RN3") (pin "6") (pinfunction "1_6") (pintype "passive"))
    )
    (net (code "94") (name "DATA5") (class "Default")
      (node (ref "IC1") (pin "14") (pinfunction "6D_14") (pintype "input"))
      (node (ref "IC1") (pin "15") (pinfunction "6Q_15") (pintype "tri_state"))
      (node (ref "IC16") (pin "14") (pinfunction "6D_14") (pintype "input"))
      (node (ref "IC3") (pin "14") (pinfunction "6D_14") (pintype "input"))
      (node (ref "IC3") (pin "15") (pinfunction "6Q_15") (pintype "tri_state"))
      (node (ref "IC31") (pin "13") (pinfunction "B6_13") (pintype "bidirectional"))
      (node (ref "IC5") (pin "14") (pinfunction "6D_14") (pintype "input"))
      (node (ref "IC5") (pin "15") (pinfunction "6Q_15") (pintype "tri_state"))
      (node (ref "IC7") (pin "14") (pinfunction "6D_14") (pintype "input"))
      (node (ref "IC7") (pin "15") (pinfunction "6Q_15") (pintype "tri_state"))
      (node (ref "JP5") (pin "13") (pinfunction "13_13") (pintype "passive"))
      (node (ref "RN3") (pin "7") (pinfunction "1_7") (pintype "passive"))
    )
    (net (code "95") (name "DATA6") (class "Default")
      (node (ref "IC1") (pin "16") (pinfunction "7Q_16") (pintype "tri_state"))
      (node (ref "IC1") (pin "17") (pinfunction "7D_17") (pintype "input"))
      (node (ref "IC16") (pin "17") (pinfunction "7D_17") (pintype "input"))
      (node (ref "IC3") (pin "16") (pinfunction "7Q_16") (pintype "tri_state"))
      (node (ref "IC3") (pin "17") (pinfunction "7D_17") (pintype "input"))
      (node (ref "IC31") (pin "12") (pinfunction "B7_12") (pintype "bidirectional"))
      (node (ref "IC5") (pin "16") (pinfunction "7Q_16") (pintype "tri_state"))
      (node (ref "IC5") (pin "17") (pinfunction "7D_17") (pintype "input"))
      (node (ref "IC7") (pin "16") (pinfunction "7Q_16") (pintype "tri_state"))
      (node (ref "IC7") (pin "17") (pinfunction "7D_17") (pintype "input"))
      (node (ref "JP5") (pin "15") (pinfunction "15_15") (pintype "passive"))
      (node (ref "RN3") (pin "8") (pinfunction "1_8") (pintype "passive"))
    )
    (net (code "96") (name "DATA7") (class "Default")
      (node (ref "IC1") (pin "18") (pinfunction "8D_18") (pintype "input"))
      (node (ref "IC1") (pin "19") (pinfunction "8Q_19") (pintype "tri_state"))
      (node (ref "IC16") (pin "18") (pinfunction "8D_18") (pintype "input"))
      (node (ref "IC3") (pin "18") (pinfunction "8D_18") (pintype "input"))
      (node (ref "IC3") (pin "19") (pinfunction "8Q_19") (pintype "tri_state"))
      (node (ref "IC31") (pin "11") (pinfunction "B8_11") (pintype "bidirectional"))
      (node (ref "IC5") (pin "18") (pinfunction "8D_18") (pintype "input"))
      (node (ref "IC5") (pin "19") (pinfunction "8Q_19") (pintype "tri_state"))
      (node (ref "IC7") (pin "18") (pinfunction "8D_18") (pintype "input"))
      (node (ref "IC7") (pin "19") (pinfunction "8Q_19") (pintype "tri_state"))
      (node (ref "JP5") (pin "17") (pinfunction "17_17") (pintype "passive"))
      (node (ref "RN3") (pin "9") (pinfunction "1_9") (pintype "passive"))
    )
    (net (code "97") (name "DATA8") (class "Default")
      (node (ref "IC17") (pin "3") (pinfunction "1D_3") (pintype "input"))
      (node (ref "IC2") (pin "2") (pinfunction "1Q_2") (pintype "tri_state"))
      (node (ref "IC2") (pin "3") (pinfunction "1D_3") (pintype "input"))
      (node (ref "IC29") (pin "18") (pinfunction "B1_18") (pintype "bidirectional"))
      (node (ref "IC30") (pin "18") (pinfunction "B1_18") (pintype "bidirectional"))
      (node (ref "IC4") (pin "2") (pinfunction "1Q_2") (pintype "tri_state"))
      (node (ref "IC4") (pin "3") (pinfunction "1D_3") (pintype "input"))
      (node (ref "IC6") (pin "2") (pinfunction "1Q_2") (pintype "tri_state"))
      (node (ref "IC6") (pin "3") (pinfunction "1D_3") (pintype "input"))
      (node (ref "IC8") (pin "2") (pinfunction "1Q_2") (pintype "tri_state"))
      (node (ref "IC8") (pin "3") (pinfunction "1D_3") (pintype "input"))
      (node (ref "JP5") (pin "4") (pinfunction "4_4") (pintype "passive"))
      (node (ref "RN4") (pin "2") (pinfunction "1_2") (pintype "passive"))
    )
    (net (code "98") (name "DATA9") (class "Default")
      (node (ref "IC17") (pin "4") (pinfunction "2D_4") (pintype "input"))
      (node (ref "IC2") (pin "4") (pinfunction "2D_4") (pintype "input"))
      (node (ref "IC2") (pin "5") (pinfunction "2Q_5") (pintype "tri_state"))
      (node (ref "IC29") (pin "17") (pinfunction "B2_17") (pintype "bidirectional"))
      (node (ref "IC30") (pin "17") (pinfunction "B2_17") (pintype "bidirectional"))
      (node (ref "IC4") (pin "4") (pinfunction "2D_4") (pintype "input"))
      (node (ref "IC4") (pin "5") (pinfunction "2Q_5") (pintype "tri_state"))
      (node (ref "IC6") (pin "4") (pinfunction "2D_4") (pintype "input"))
      (node (ref "IC6") (pin "5") (pinfunction "2Q_5") (pintype "tri_state"))
      (node (ref "IC8") (pin "4") (pinfunction "2D_4") (pintype "input"))
      (node (ref "IC8") (pin "5") (pinfunction "2Q_5") (pintype "tri_state"))
      (node (ref "JP5") (pin "6") (pinfunction "6_6") (pintype "passive"))
      (node (ref "RN4") (pin "3") (pinfunction "1_3") (pintype "passive"))
    )
    (net (code "99") (name "DATA10") (class "Default")
      (node (ref "IC17") (pin "7") (pinfunction "3D_7") (pintype "input"))
      (node (ref "IC2") (pin "6") (pinfunction "3Q_6") (pintype "tri_state"))
      (node (ref "IC2") (pin "7") (pinfunction "3D_7") (pintype "input"))
      (node (ref "IC29") (pin "16") (pinfunction "B3_16") (pintype "bidirectional"))
      (node (ref "IC30") (pin "16") (pinfunction "B3_16") (pintype "bidirectional"))
      (node (ref "IC4") (pin "6") (pinfunction "3Q_6") (pintype "tri_state"))
      (node (ref "IC4") (pin "7") (pinfunction "3D_7") (pintype "input"))
      (node (ref "IC6") (pin "6") (pinfunction "3Q_6") (pintype "tri_state"))
      (node (ref "IC6") (pin "7") (pinfunction "3D_7") (pintype "input"))
      (node (ref "IC8") (pin "6") (pinfunction "3Q_6") (pintype "tri_state"))
      (node (ref "IC8") (pin "7") (pinfunction "3D_7") (pintype "input"))
      (node (ref "JP5") (pin "8") (pinfunction "8_8") (pintype "passive"))
      (node (ref "RN4") (pin "4") (pinfunction "1_4") (pintype "passive"))
    )
    (net (code "100") (name "DATA11") (class "Default")
      (node (ref "IC17") (pin "8") (pinfunction "4D_8") (pintype "input"))
      (node (ref "IC2") (pin "8") (pinfunction "4D_8") (pintype "input"))
      (node (ref "IC2") (pin "9") (pinfunction "4Q_9") (pintype "tri_state"))
      (node (ref "IC29") (pin "15") (pinfunction "B4_15") (pintype "bidirectional"))
      (node (ref "IC30") (pin "15") (pinfunction "B4_15") (pintype "bidirectional"))
      (node (ref "IC4") (pin "8") (pinfunction "4D_8") (pintype "input"))
      (node (ref "IC4") (pin "9") (pinfunction "4Q_9") (pintype "tri_state"))
      (node (ref "IC6") (pin "8") (pinfunction "4D_8") (pintype "input"))
      (node (ref "IC6") (pin "9") (pinfunction "4Q_9") (pintype "tri_state"))
      (node (ref "IC8") (pin "8") (pinfunction "4D_8") (pintype "input"))
      (node (ref "IC8") (pin "9") (pinfunction "4Q_9") (pintype "tri_state"))
      (node (ref "JP5") (pin "10") (pinfunction "10_10") (pintype "passive"))
      (node (ref "RN4") (pin "5") (pinfunction "1_5") (pintype "passive"))
    )
    (net (code "101") (name "DATA12") (class "Default")
      (node (ref "IC17") (pin "13") (pinfunction "5D_13") (pintype "input"))
      (node (ref "IC2") (pin "12") (pinfunction "5Q_12") (pintype "tri_state"))
      (node (ref "IC2") (pin "13") (pinfunction "5D_13") (pintype "input"))
      (node (ref "IC29") (pin "14") (pinfunction "B5_14") (pintype "bidirectional"))
      (node (ref "IC30") (pin "14") (pinfunction "B5_14") (pintype "bidirectional"))
      (node (ref "IC4") (pin "12") (pinfunction "5Q_12") (pintype "tri_state"))
      (node (ref "IC4") (pin "13") (pinfunction "5D_13") (pintype "input"))
      (node (ref "IC6") (pin "12") (pinfunction "5Q_12") (pintype "tri_state"))
      (node (ref "IC6") (pin "13") (pinfunction "5D_13") (pintype "input"))
      (node (ref "IC8") (pin "12") (pinfunction "5Q_12") (pintype "tri_state"))
      (node (ref "IC8") (pin "13") (pinfunction "5D_13") (pintype "input"))
      (node (ref "JP5") (pin "12") (pinfunction "12_12") (pintype "passive"))
      (node (ref "RN4") (pin "6") (pinfunction "1_6") (pintype "passive"))
    )
    (net (code "102") (name "DATA13") (class "Default")
      (node (ref "IC17") (pin "14") (pinfunction "6D_14") (pintype "input"))
      (node (ref "IC2") (pin "14") (pinfunction "6D_14") (pintype "input"))
      (node (ref "IC2") (pin "15") (pinfunction "6Q_15") (pintype "tri_state"))
      (node (ref "IC29") (pin "13") (pinfunction "B6_13") (pintype "bidirectional"))
      (node (ref "IC30") (pin "13") (pinfunction "B6_13") (pintype "bidirectional"))
      (node (ref "IC4") (pin "14") (pinfunction "6D_14") (pintype "input"))
      (node (ref "IC4") (pin "15") (pinfunction "6Q_15") (pintype "tri_state"))
      (node (ref "IC6") (pin "14") (pinfunction "6D_14") (pintype "input"))
      (node (ref "IC6") (pin "15") (pinfunction "6Q_15") (pintype "tri_state"))
      (node (ref "IC8") (pin "14") (pinfunction "6D_14") (pintype "input"))
      (node (ref "IC8") (pin "15") (pinfunction "6Q_15") (pintype "tri_state"))
      (node (ref "JP5") (pin "14") (pinfunction "14_14") (pintype "passive"))
      (node (ref "RN4") (pin "7") (pinfunction "1_7") (pintype "passive"))
    )
    (net (code "103") (name "DATA14") (class "Default")
      (node (ref "IC17") (pin "17") (pinfunction "7D_17") (pintype "input"))
      (node (ref "IC2") (pin "16") (pinfunction "7Q_16") (pintype "tri_state"))
      (node (ref "IC2") (pin "17") (pinfunction "7D_17") (pintype "input"))
      (node (ref "IC29") (pin "12") (pinfunction "B7_12") (pintype "bidirectional"))
      (node (ref "IC30") (pin "12") (pinfunction "B7_12") (pintype "bidirectional"))
      (node (ref "IC4") (pin "16") (pinfunction "7Q_16") (pintype "tri_state"))
      (node (ref "IC4") (pin "17") (pinfunction "7D_17") (pintype "input"))
      (node (ref "IC6") (pin "16") (pinfunction "7Q_16") (pintype "tri_state"))
      (node (ref "IC6") (pin "17") (pinfunction "7D_17") (pintype "input"))
      (node (ref "IC8") (pin "16") (pinfunction "7Q_16") (pintype "tri_state"))
      (node (ref "IC8") (pin "17") (pinfunction "7D_17") (pintype "input"))
      (node (ref "JP5") (pin "16") (pinfunction "16_16") (pintype "passive"))
      (node (ref "RN4") (pin "8") (pinfunction "1_8") (pintype "passive"))
    )
    (net (code "104") (name "DATA15") (class "Default")
      (node (ref "IC17") (pin "18") (pinfunction "8D_18") (pintype "input"))
      (node (ref "IC2") (pin "18") (pinfunction "8D_18") (pintype "input"))
      (node (ref "IC2") (pin "19") (pinfunction "8Q_19") (pintype "tri_state"))
      (node (ref "IC29") (pin "11") (pinfunction "B8_11") (pintype "bidirectional"))
      (node (ref "IC30") (pin "11") (pinfunction "B8_11") (pintype "bidirectional"))
      (node (ref "IC4") (pin "18") (pinfunction "8D_18") (pintype "input"))
      (node (ref "IC4") (pin "19") (pinfunction "8Q_19") (pintype "tri_state"))
      (node (ref "IC6") (pin "18") (pinfunction "8D_18") (pintype "input"))
      (node (ref "IC6") (pin "19") (pinfunction "8Q_19") (pintype "tri_state"))
      (node (ref "IC8") (pin "18") (pinfunction "8D_18") (pintype "input"))
      (node (ref "IC8") (pin "19") (pinfunction "8Q_19") (pintype "tri_state"))
      (node (ref "JP5") (pin "18") (pinfunction "18_18") (pintype "passive"))
      (node (ref "RN4") (pin "9") (pinfunction "1_9") (pintype "passive"))
    )
    (net (code "105") (name "GND") (class "Default")
      (node (ref "C1") (pin "2") (pinfunction "2_2") (pintype "passive"))
      (node (ref "C2") (pin "2") (pinfunction "2_2") (pintype "passive"))
      (node (ref "C21") (pin "2") (pinfunction "2_2") (pintype "passive"))
      (node (ref "C22") (pin "2") (pinfunction "2_2") (pintype "passive"))
      (node (ref "C23") (pin "2") (pinfunction "2_2") (pintype "passive"))
      (node (ref "C24") (pin "2") (pinfunction "2_2") (pintype "passive"))
      (node (ref "C25") (pin "2") (pinfunction "2_2") (pintype "passive"))
      (node (ref "C26") (pin "2") (pinfunction "2_2") (pintype "passive"))
      (node (ref "C27") (pin "2") (pinfunction "2_2") (pintype "passive"))
      (node (ref "C28") (pin "2") (pinfunction "2_2") (pintype "passive"))
      (node (ref "C29") (pin "2") (pinfunction "2_2") (pintype "passive"))
      (node (ref "C3") (pin "2") (pinfunction "2_2") (pintype "passive"))
      (node (ref "C30") (pin "2") (pinfunction "2_2") (pintype "passive"))
      (node (ref "C31") (pin "2") (pinfunction "2_2") (pintype "passive"))
      (node (ref "C32") (pin "2") (pinfunction "2_2") (pintype "passive"))
      (node (ref "C33") (pin "2") (pinfunction "2_2") (pintype "passive"))
      (node (ref "C34") (pin "2") (pinfunction "2_2") (pintype "passive"))
      (node (ref "C35") (pin "2") (pinfunction "2_2") (pintype "passive"))
      (node (ref "C36") (pin "2") (pinfunction "2_2") (pintype "passive"))
      (node (ref "C37") (pin "2") (pinfunction "2_2") (pintype "passive"))
      (node (ref "C38") (pin "2") (pinfunction "2_2") (pintype "passive"))
      (node (ref "C39") (pin "2") (pinfunction "2_2") (pintype "passive"))
      (node (ref "C4") (pin "2") (pinfunction "2_2") (pintype "passive"))
      (node (ref "C40") (pin "2") (pinfunction "2_2") (pintype "passive"))
      (node (ref "IC11") (pin "15") (pinfunction "G_15") (pintype "input"))
      (node (ref "IC19") (pin "10") (pinfunction "I1_10") (pintype "input"))
      (node (ref "IC19") (pin "12") (pinfunction "I0_12") (pintype "input"))
      (node (ref "IC19") (pin "13") (pinfunction "I1_13") (pintype "input"))
      (node (ref "IC19") (pin "9") (pinfunction "I0_9") (pintype "input"))
      (node (ref "IC41") (pin "1") (pinfunction "G_1") (pintype "input"))
      (node (ref "IC41") (pin "10") (pinfunction "GND_10") (pintype "power_in"))
      (node (ref "IC41") (pin "19") (pinfunction "G_19") (pintype "input"))
      (node (ref "IC9") (pin "15") (pinfunction "G_15") (pintype "input"))
      (node (ref "JP5") (pin "1") (pinfunction "1_1") (pintype "passive"))
      (node (ref "JP5") (pin "2") (pinfunction "2_2") (pintype "passive"))
      (node (ref "JP5") (pin "27") (pinfunction "27_27") (pintype "passive"))
      (node (ref "JP5") (pin "28") (pinfunction "28_28") (pintype "passive"))
      (node (ref "X1") (pin "A1") (pinfunction "B_A1") (pintype "passive"))
      (node (ref "X1") (pin "A32") (pinfunction "B_A32") (pintype "passive"))
      (node (ref "X1") (pin "B1") (pinfunction "B_B1") (pintype "passive"))
      (node (ref "X1") (pin "B32") (pinfunction "B_B32") (pintype "passive"))
      (node (ref "X1") (pin "C1") (pinfunction "B_C1") (pintype "passive"))
      (node (ref "X1") (pin "C32") (pinfunction "B_C32") (pintype "passive"))
    )
    (net (code "106") (name "HLSWAP") (class "Default")
      (node (ref "IC19") (pin "1") (pinfunction "I0_1") (pintype "input"))
      (node (ref "IC19") (pin "2") (pinfunction "I1_2") (pintype "input"))
      (node (ref "IC20") (pin "13") (pinfunction "I1_13") (pintype "input"))
      (node (ref "X1") (pin "A30") (pinfunction "B_A30") (pintype "passive"))
    )
    (net (code "107") (name "Net-(IC9B-Y0)") (class "Default")
      (node (ref "IC9") (pin "12") (pinfunction "Y0_12") (pintype "output"))
      (node (ref "RD-BRDSEL") (pin "1") (pinfunction "1_1") (pintype "passive"))
    )
    (net (code "108") (name "Net-(IC9B-Y1)") (class "Default")
      (node (ref "IC9") (pin "11") (pinfunction "Y1_11") (pintype "output"))
      (node (ref "RD-BRDSEL") (pin "3") (pinfunction "3_3") (pintype "passive"))
    )
    (net (code "109") (name "Net-(IC9B-Y2)") (class "Default")
      (node (ref "IC9") (pin "10") (pinfunction "Y2_10") (pintype "output"))
      (node (ref "RD-BRDSEL") (pin "5") (pinfunction "5_5") (pintype "passive"))
    )
    (net (code "110") (name "Net-(IC9B-Y3)") (class "Default")
      (node (ref "IC9") (pin "9") (pinfunction "Y3_9") (pintype "output"))
      (node (ref "RD-BRDSEL") (pin "7") (pinfunction "7_7") (pintype "passive"))
    )
    (net (code "111") (name "Net-(IC10A-O)") (class "Default")
      (node (ref "IC1") (pin "1") (pinfunction "OC_1") (pintype "input"))
      (node (ref "IC10") (pin "3") (pinfunction "O_3") (pintype "output"))
    )
    (net (code "112") (name "Net-(IC10B-O)") (class "Default")
      (node (ref "IC10") (pin "6") (pinfunction "O_6") (pintype "output"))
      (node (ref "IC2") (pin "1") (pinfunction "OC_1") (pintype "input"))
    )
    (net (code "113") (name "Net-(IC10C-O)") (class "Default")
      (node (ref "IC10") (pin "8") (pinfunction "O_8") (pintype "output"))
      (node (ref "IC5") (pin "1") (pinfunction "OC_1") (pintype "input"))
    )
    (net (code "114") (name "Net-(IC10D-O)") (class "Default")
      (node (ref "IC10") (pin "11") (pinfunction "O_11") (pintype "output"))
      (node (ref "IC6") (pin "1") (pinfunction "OC_1") (pintype "input"))
    )
    (net (code "115") (name "Net-(IC11B-Y0)") (class "Default")
      (node (ref "IC11") (pin "12") (pinfunction "Y0_12") (pintype "output"))
      (node (ref "WR-BRDSEL") (pin "1") (pinfunction "1_1") (pintype "passive"))
    )
    (net (code "116") (name "Net-(IC11B-Y1)") (class "Default")
      (node (ref "IC11") (pin "11") (pinfunction "Y1_11") (pintype "output"))
      (node (ref "WR-BRDSEL") (pin "3") (pinfunction "3_3") (pintype "passive"))
    )
    (net (code "117") (name "Net-(IC11B-Y2)") (class "Default")
      (node (ref "IC11") (pin "10") (pinfunction "Y2_10") (pintype "output"))
      (node (ref "WR-BRDSEL") (pin "5") (pinfunction "5_5") (pintype "passive"))
    )
    (net (code "118") (name "Net-(IC11B-Y3)") (class "Default")
      (node (ref "IC11") (pin "9") (pinfunction "Y3_9") (pintype "output"))
      (node (ref "WR-BRDSEL") (pin "7") (pinfunction "7_7") (pintype "passive"))
    )
    (net (code "119") (name "Net-(IC13E-O)") (class "Default")
      (node (ref "IC13") (pin "10") (pinfunction "O_10") (pintype "output"))
      (node (ref "IC18") (pin "1") (pinfunction "G_1") (pintype "input"))
    )
    (net (code "120") (name "Net-(IC13F-I)") (class "Default")
      (node (ref "ADDRCLK-SEL") (pin "2") (pinfunction "2_2") (pintype "passive"))
      (node (ref "ADDRCLK-SEL") (pin "4") (pinfunction "4_4") (pintype "passive"))
      (node (ref "ADDRCLK-SEL") (pin "6") (pinfunction "6_6") (pintype "passive"))
      (node (ref "ADDRCLK-SEL") (pin "8") (pinfunction "8_8") (pintype "passive"))
      (node (ref "IC13") (pin "13") (pinfunction "I_13") (pintype "input"))
    )
    (net (code "121") (name "Net-(IC13F-O)") (class "Default")
      (node (ref "IC13") (pin "12") (pinfunction "O_12") (pintype "output"))
      (node (ref "IC16") (pin "11") (pinfunction "CLK_11") (pintype "input"))
      (node (ref "IC17") (pin "11") (pinfunction "CLK_11") (pintype "input"))
    )
    (net (code "122") (name "Net-(IC14A-O)") (class "Default")
      (node (ref "IC14") (pin "3") (pinfunction "O_3") (pintype "output"))
      (node (ref "IC3") (pin "1") (pinfunction "OC_1") (pintype "input"))
    )
    (net (code "123") (name "Net-(IC14B-O)") (class "Default")
      (node (ref "IC14") (pin "6") (pinfunction "O_6") (pintype "output"))
      (node (ref "IC4") (pin "1") (pinfunction "OC_1") (pintype "input"))
    )
    (net (code "124") (name "Net-(IC14C-O)") (class "Default")
      (node (ref "IC14") (pin "8") (pinfunction "O_8") (pintype "output"))
      (node (ref "IC7") (pin "1") (pinfunction "OC_1") (pintype "input"))
    )
    (net (code "125") (name "Net-(IC14D-O)") (class "Default")
      (node (ref "IC14") (pin "11") (pinfunction "O_11") (pintype "output"))
      (node (ref "IC8") (pin "1") (pinfunction "OC_1") (pintype "input"))
    )
    (net (code "126") (name "Net-(IC16A-OC)") (class "Default")
      (node (ref "ADDOUT-SEL") (pin "2") (pinfunction "2_2") (pintype "passive"))
      (node (ref "ADDOUT-SEL") (pin "4") (pinfunction "4_4") (pintype "passive"))
      (node (ref "ADDOUT-SEL") (pin "6") (pinfunction "6_6") (pintype "passive"))
      (node (ref "ADDOUT-SEL") (pin "8") (pinfunction "8_8") (pintype "passive"))
      (node (ref "IC16") (pin "1") (pinfunction "OC_1") (pintype "input"))
      (node (ref "IC17") (pin "1") (pinfunction "OC_1") (pintype "input"))
    )
    (net (code "127") (name "Net-(IC18A-Y0)") (class "Default")
      (node (ref "ADDRCLK-SEL") (pin "1") (pinfunction "1_1") (pintype "passive"))
      (node (ref "IC18") (pin "4") (pinfunction "Y0_4") (pintype "output"))
    )
    (net (code "128") (name "Net-(IC18A-Y1)") (class "Default")
      (node (ref "ADDRCLK-SEL") (pin "3") (pinfunction "3_3") (pintype "passive"))
      (node (ref "IC18") (pin "5") (pinfunction "Y1_5") (pintype "output"))
    )
    (net (code "129") (name "Net-(IC18A-Y2)") (class "Default")
      (node (ref "ADDRCLK-SEL") (pin "5") (pinfunction "5_5") (pintype "passive"))
      (node (ref "IC18") (pin "6") (pinfunction "Y2_6") (pintype "output"))
    )
    (net (code "130") (name "Net-(IC18A-Y3)") (class "Default")
      (node (ref "ADDRCLK-SEL") (pin "7") (pinfunction "7_7") (pintype "passive"))
      (node (ref "IC18") (pin "7") (pinfunction "Y3_7") (pintype "output"))
    )
    (net (code "131") (name "Net-(IC18B-G)") (class "Default")
      (node (ref "IC18") (pin "15") (pinfunction "G_15") (pintype "input"))
      (node (ref "IC19") (pin "6") (pinfunction "O_6") (pintype "output"))
    )
    (net (code "132") (name "Net-(IC18B-Y0)") (class "Default")
      (node (ref "ADDOUT-SEL") (pin "1") (pinfunction "1_1") (pintype "passive"))
      (node (ref "IC18") (pin "12") (pinfunction "Y0_12") (pintype "output"))
    )
    (net (code "133") (name "Net-(IC18B-Y1)") (class "Default")
      (node (ref "ADDOUT-SEL") (pin "3") (pinfunction "3_3") (pintype "passive"))
      (node (ref "IC18") (pin "11") (pinfunction "Y1_11") (pintype "output"))
    )
    (net (code "134") (name "Net-(IC18B-Y2)") (class "Default")
      (node (ref "ADDOUT-SEL") (pin "5") (pinfunction "5_5") (pintype "passive"))
      (node (ref "IC18") (pin "10") (pinfunction "Y2_10") (pintype "output"))
    )
    (net (code "135") (name "Net-(IC18B-Y3)") (class "Default")
      (node (ref "ADDOUT-SEL") (pin "7") (pinfunction "7_7") (pintype "passive"))
      (node (ref "IC18") (pin "9") (pinfunction "Y3_9") (pintype "output"))
    )
    (net (code "136") (name "Net-(IC19A-O)") (class "Default")
      (node (ref "IC19") (pin "3") (pinfunction "O_3") (pintype "output"))
      (node (ref "IC20") (pin "9") (pinfunction "I0_9") (pintype "input"))
    )
    (net (code "137") (name "Net-(IC20A-O)") (class "Default")
      (node (ref "IC20") (pin "10") (pinfunction "I1_10") (pintype "input"))
      (node (ref "IC20") (pin "12") (pinfunction "I0_12") (pintype "input"))
      (node (ref "IC20") (pin "3") (pinfunction "O_3") (pintype "output"))
      (node (ref "IC20") (pin "4") (pinfunction "I0_4") (pintype "input"))
      (node (ref "IC20") (pin "5") (pinfunction "I1_5") (pintype "input"))
    )
    (net (code "138") (name "Net-(IC20B-O)") (class "Default")
      (node (ref "IC20") (pin "6") (pinfunction "O_6") (pintype "output"))
      (node (ref "IC29") (pin "19") (pinfunction "G_19") (pintype "input"))
    )
    (net (code "139") (name "Net-(IC20C-O)") (class "Default")
      (node (ref "IC20") (pin "8") (pinfunction "O_8") (pintype "output"))
      (node (ref "IC31") (pin "19") (pinfunction "G_19") (pintype "input"))
    )
    (net (code "140") (name "Net-(IC20D-O)") (class "Default")
      (node (ref "IC20") (pin "11") (pinfunction "O_11") (pintype "output"))
      (node (ref "IC30") (pin "19") (pinfunction "G_19") (pintype "input"))
    )
    (net (code "141") (name "RA0") (class "Default")
      (node (ref "IC18") (pin "14") (pinfunction "A_14") (pintype "input"))
      (node (ref "IC18") (pin "2") (pinfunction "A_2") (pintype "input"))
      (node (ref "X1") (pin "B6") (pinfunction "B_B6") (pintype "passive"))
    )
    (net (code "142") (name "RA1") (class "Default")
      (node (ref "IC18") (pin "13") (pinfunction "B_13") (pintype "input"))
      (node (ref "IC18") (pin "3") (pinfunction "B_3") (pintype "input"))
      (node (ref "X1") (pin "B5") (pinfunction "B_B5") (pintype "passive"))
    )
    (net (code "143") (name "RACLK") (class "Default")
      (node (ref "IC13") (pin "11") (pinfunction "I_11") (pintype "input"))
      (node (ref "X1") (pin "B4") (pinfunction "B_B4") (pintype "passive"))
    )
    (net (code "144") (name "RAOUT") (class "Default")
      (node (ref "IC19") (pin "4") (pinfunction "I0_4") (pintype "input"))
      (node (ref "IC19") (pin "5") (pinfunction "I1_5") (pintype "input"))
      (node (ref "IC41") (pin "12") (pinfunction "Y4_12") (pintype "tri_state"))
    )
    (net (code "145") (name "RDN") (class "Default")
      (node (ref "IC41") (pin "14") (pinfunction "Y3_14") (pintype "tri_state"))
    )
    (net (code "146") (name "RDSEL") (class "Default")
      (node (ref "IC20") (pin "1") (pinfunction "I0_1") (pintype "input"))
      (node (ref "IC9") (pin "1") (pinfunction "G_1") (pintype "input"))
      (node (ref "RD-BRDSEL") (pin "2") (pinfunction "2_2") (pintype "passive"))
      (node (ref "RD-BRDSEL") (pin "4") (pinfunction "4_4") (pintype "passive"))
      (node (ref "RD-BRDSEL") (pin "6") (pinfunction "6_6") (pintype "passive"))
      (node (ref "RD-BRDSEL") (pin "8") (pinfunction "8_8") (pintype "passive"))
    )
    (net (code "147") (name "RESET") (class "Default")
      (node (ref "IC41") (pin "18") (pinfunction "Y1_18") (pintype "tri_state"))
    )
    (net (code "148") (name "RRD0") (class "Default")
      (node (ref "IC9") (pin "2") (pinfunction "A_2") (pintype "input"))
      (node (ref "X1") (pin "B12") (pinfunction "B_B12") (pintype "passive"))
    )
    (net (code "149") (name "RRD1") (class "Default")
      (node (ref "IC9") (pin "3") (pinfunction "B_3") (pintype "input"))
      (node (ref "X1") (pin "B13") (pinfunction "B_B13") (pintype "passive"))
    )
    (net (code "150") (name "RRD2") (class "Default")
      (node (ref "IC9") (pin "14") (pinfunction "A_14") (pintype "input"))
      (node (ref "X1") (pin "B14") (pinfunction "B_B14") (pintype "passive"))
    )
    (net (code "151") (name "RRD3") (class "Default")
      (node (ref "IC9") (pin "13") (pinfunction "B_13") (pintype "input"))
      (node (ref "X1") (pin "B15") (pinfunction "B_B15") (pintype "passive"))
    )
    (net (code "152") (name "RRDH") (class "Default")
      (node (ref "IC13") (pin "5") (pinfunction "I_5") (pintype "input"))
      (node (ref "IC41") (pin "7") (pinfunction "Y2_7") (pintype "tri_state"))
    )
    (net (code "153") (name "RRDL") (class "Default")
      (node (ref "IC13") (pin "1") (pinfunction "I_1") (pintype "input"))
      (node (ref "IC41") (pin "3") (pinfunction "Y4_3") (pintype "tri_state"))
    )
    (net (code "154") (name "RUP") (class "Default")
      (node (ref "IC41") (pin "16") (pinfunction "Y2_16") (pintype "tri_state"))
    )
    (net (code "155") (name "RWR0") (class "Default")
      (node (ref "IC11") (pin "2") (pinfunction "A_2") (pintype "input"))
      (node (ref "X1") (pin "B16") (pinfunction "B_B16") (pintype "passive"))
    )
    (net (code "156") (name "RWR1") (class "Default")
      (node (ref "IC11") (pin "3") (pinfunction "B_3") (pintype "input"))
      (node (ref "X1") (pin "B17") (pinfunction "B_B17") (pintype "passive"))
    )
    (net (code "157") (name "RWR2") (class "Default")
      (node (ref "IC11") (pin "14") (pinfunction "A_14") (pintype "input"))
      (node (ref "X1") (pin "B18") (pinfunction "B_B18") (pintype "passive"))
    )
    (net (code "158") (name "RWR3") (class "Default")
      (node (ref "IC11") (pin "13") (pinfunction "B_13") (pintype "input"))
      (node (ref "X1") (pin "B19") (pinfunction "B_B19") (pintype "passive"))
    )
    (net (code "159") (name "RWRH") (class "Default")
      (node (ref "IC13") (pin "9") (pinfunction "I_9") (pintype "input"))
      (node (ref "IC41") (pin "9") (pinfunction "Y1_9") (pintype "tri_state"))
    )
    (net (code "160") (name "RWRL") (class "Default")
      (node (ref "IC13") (pin "3") (pinfunction "I_3") (pintype "input"))
      (node (ref "IC41") (pin "5") (pinfunction "Y3_5") (pintype "tri_state"))
    )
    (net (code "161") (name "VCC") (class "Default")
      (node (ref "C1") (pin "1") (pinfunction "1_1") (pintype "passive"))
      (node (ref "C2") (pin "1") (pinfunction "1_1") (pintype "passive"))
      (node (ref "C21") (pin "1") (pinfunction "1_1") (pintype "passive"))
      (node (ref "C22") (pin "1") (pinfunction "1_1") (pintype "passive"))
      (node (ref "C23") (pin "1") (pinfunction "1_1") (pintype "passive"))
      (node (ref "C24") (pin "1") (pinfunction "1_1") (pintype "passive"))
      (node (ref "C25") (pin "1") (pinfunction "1_1") (pintype "passive"))
      (node (ref "C26") (pin "1") (pinfunction "1_1") (pintype "passive"))
      (node (ref "C27") (pin "1") (pinfunction "1_1") (pintype "passive"))
      (node (ref "C28") (pin "1") (pinfunction "1_1") (pintype "passive"))
      (node (ref "C29") (pin "1") (pinfunction "1_1") (pintype "passive"))
      (node (ref "C3") (pin "1") (pinfunction "1_1") (pintype "passive"))
      (node (ref "C30") (pin "1") (pinfunction "1_1") (pintype "passive"))
      (node (ref "C31") (pin "1") (pinfunction "1_1") (pintype "passive"))
      (node (ref "C32") (pin "1") (pinfunction "1_1") (pintype "passive"))
      (node (ref "C33") (pin "1") (pinfunction "1_1") (pintype "passive"))
      (node (ref "C34") (pin "1") (pinfunction "1_1") (pintype "passive"))
      (node (ref "C35") (pin "1") (pinfunction "1_1") (pintype "passive"))
      (node (ref "C36") (pin "1") (pinfunction "1_1") (pintype "passive"))
      (node (ref "C37") (pin "1") (pinfunction "1_1") (pintype "passive"))
      (node (ref "C38") (pin "1") (pinfunction "1_1") (pintype "passive"))
      (node (ref "C39") (pin "1") (pinfunction "1_1") (pintype "passive"))
      (node (ref "C4") (pin "1") (pinfunction "1_1") (pintype "passive"))
      (node (ref "C40") (pin "1") (pinfunction "1_1") (pintype "passive"))
      (node (ref "IC41") (pin "20") (pinfunction "VCC_20") (pintype "power_in"))
      (node (ref "RN3") (pin "1") (pinfunction "1_1") (pintype "passive"))
      (node (ref "RN4") (pin "1") (pinfunction "1_1") (pintype "passive"))
      (node (ref "X1") (pin "A2") (pinfunction "B_A2") (pintype "passive"))
      (node (ref "X1") (pin "A31") (pinfunction "B_A31") (pintype "passive"))
      (node (ref "X1") (pin "B2") (pinfunction "B_B2") (pintype "passive"))
      (node (ref "X1") (pin "B31") (pinfunction "B_B31") (pintype "passive"))
      (node (ref "X1") (pin "C2") (pinfunction "B_C2") (pintype "passive"))
      (node (ref "X1") (pin "C31") (pinfunction "B_C31") (pintype "passive"))
    )
    (net (code "162") (name "WRSEL") (class "Default")
      (node (ref "IC11") (pin "1") (pinfunction "G_1") (pintype "input"))
      (node (ref "IC20") (pin "2") (pinfunction "I1_2") (pintype "input"))
      (node (ref "WR-BRDSEL") (pin "2") (pinfunction "2_2") (pintype "passive"))
      (node (ref "WR-BRDSEL") (pin "4") (pinfunction "4_4") (pintype "passive"))
      (node (ref "WR-BRDSEL") (pin "6") (pinfunction "6_6") (pintype "passive"))
      (node (ref "WR-BRDSEL") (pin "8") (pinfunction "8_8") (pintype "passive"))
    )
    (net (code "163") (name "unconnected-(IC19C-O-Pad8)") (class "Default")
      (node (ref "IC19") (pin "8") (pinfunction "O_8") (pintype "output"))
    )
    (net (code "164") (name "unconnected-(IC19D-O-Pad11)") (class "Default")
      (node (ref "IC19") (pin "11") (pinfunction "O_11") (pintype "output"))
    )
    (net (code "165") (name "unconnected-(X1BJ-B-PadB7)") (class "Default")
      (node (ref "X1") (pin "B7") (pinfunction "B_B7") (pintype "passive"))
    )
    (net (code "166") (name "unconnected-(X1U-B-PadA28)") (class "Default")
      (node (ref "X1") (pin "A28") (pinfunction "B_A28") (pintype "passive"))
    )
  )
)
